# cybathlon_core.net
KiCad netlist of a schematic drawn in Altium Designer
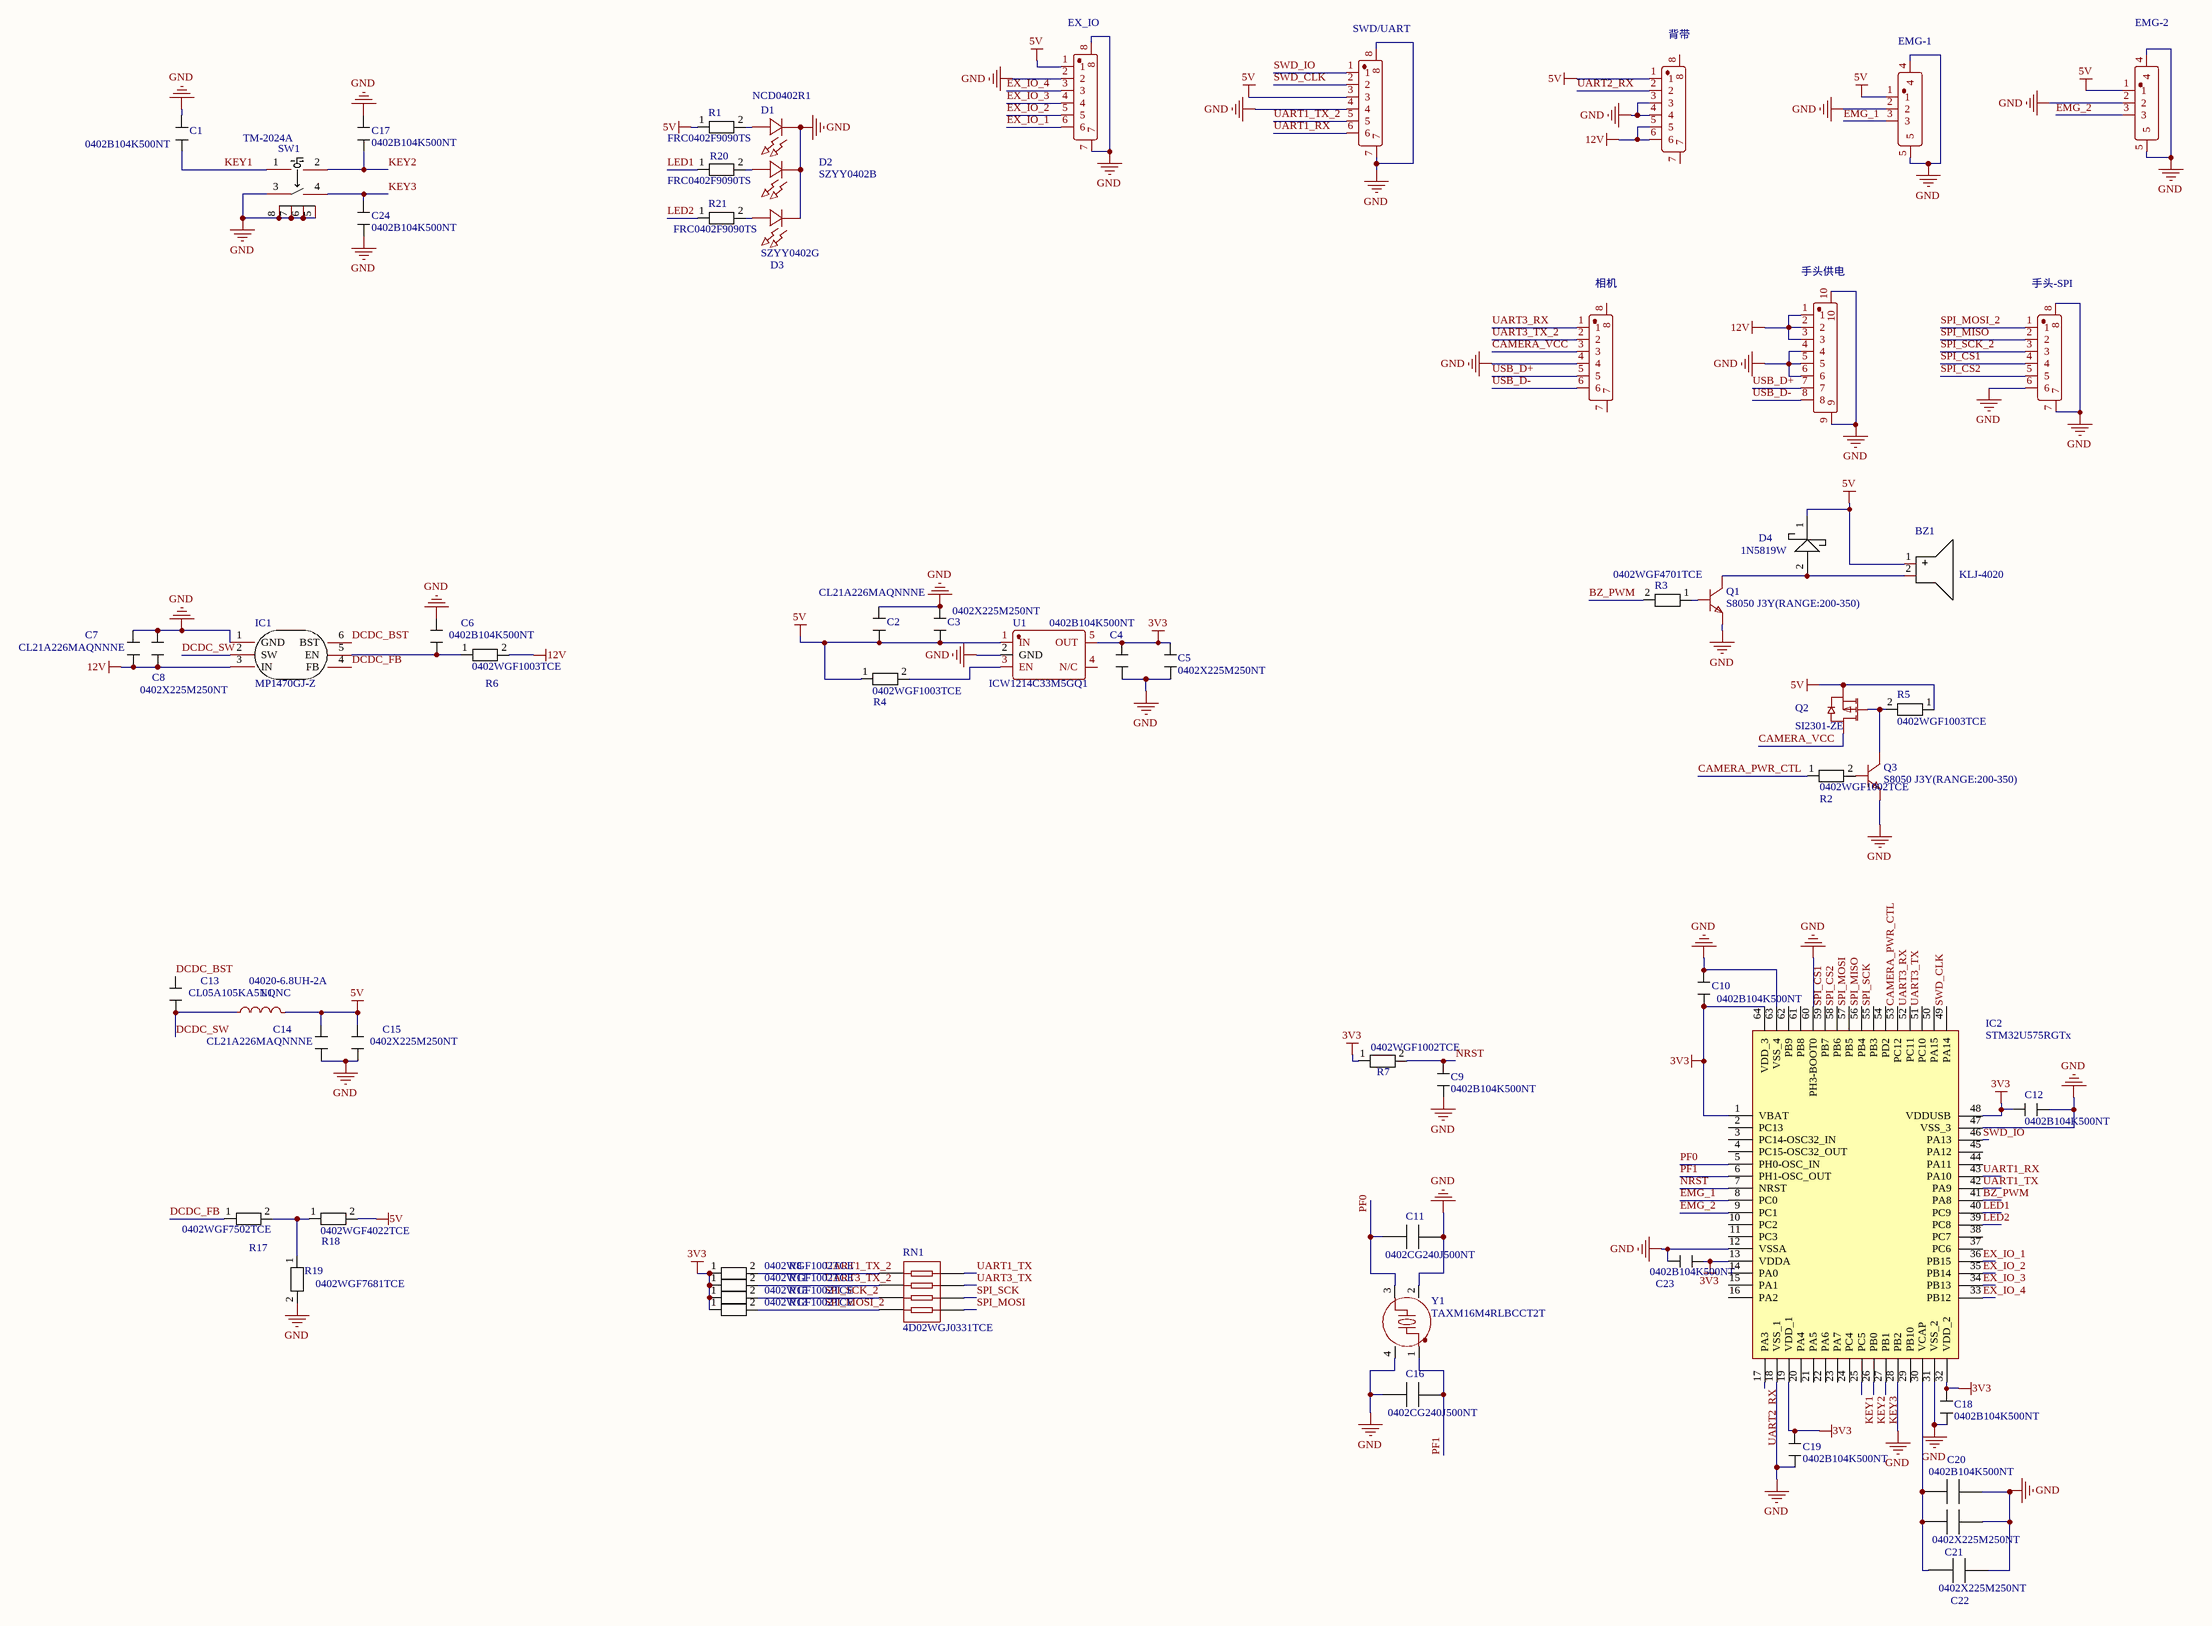
[diagram p0: cybathlon_core.SchDoc]

(export (version "E")
  (design (tool "Eeschema 10.0.6"))
  (components
    (comp (ref "BZ1")
      (value "KLJ-4020")
      (footprint "BUZ-SMD_L4.0-W4.0-P3.50-L")
      (libsource (lib "USER_RCL") (part "BUZZER_UNSOURCE"))
    )
    (comp (ref "C1") (value "0402B104K500NT") (footprint "CAP_0402") (libsource (lib "") (part "CAP_1")))
    (comp (ref "C2") (value "CL21A226MAQNNNE") (footprint "CAP_0805") (libsource (lib "") (part "CAP_1")))
    (comp (ref "C3") (value "0402X225M250NT") (footprint "CAP_0402") (libsource (lib "") (part "CAP_1")))
    (comp (ref "C4") (value "0402B104K500NT") (footprint "CAP_0402") (libsource (lib "") (part "CAP_1")))
    (comp (ref "C5") (value "0402X225M250NT") (footprint "CAP_0402") (libsource (lib "") (part "CAP_1")))
    (comp (ref "C6") (value "0402B104K500NT") (footprint "CAP_0402") (libsource (lib "") (part "CAP_1")))
    (comp (ref "C7") (value "CL21A226MAQNNNE") (footprint "CAP_0805") (libsource (lib "") (part "CAP_1")))
    (comp (ref "C8") (value "0402X225M250NT") (footprint "CAP_0402") (libsource (lib "") (part "CAP_1")))
    (comp (ref "C9") (value "0402B104K500NT") (footprint "CAP_0402") (libsource (lib "") (part "CAP_1")))
    (comp (ref "C10") (value "0402B104K500NT") (footprint "CAP_0402") (libsource (lib "") (part "CAP_1")))
    (comp (ref "C11")
      (value "0402CG240J500NT")
      (footprint "CAP_0402")
      (libsource (lib "USER_RCL") (part "CAP"))
    )
    (comp (ref "C12") (value "0402B104K500NT") (footprint "CAP_0402") (libsource (lib "") (part "CAP_1")))
    (comp (ref "C13") (value "CL05A105KA5NQNC") (footprint "CAP_0402") (libsource (lib "") (part "CAP_1")))
    (comp (ref "C14") (value "CL21A226MAQNNNE") (footprint "CAP_0805") (libsource (lib "") (part "CAP_1")))
    (comp (ref "C15") (value "0402X225M250NT") (footprint "CAP_0402") (libsource (lib "") (part "CAP_1")))
    (comp (ref "C16")
      (value "0402CG240J500NT")
      (footprint "CAP_0402")
      (libsource (lib "USER_RCL") (part "CAP"))
    )
    (comp (ref "C17") (value "0402B104K500NT") (footprint "CAP_0402") (libsource (lib "") (part "CAP_1")))
    (comp (ref "C18") (value "0402B104K500NT") (footprint "CAP_0402") (libsource (lib "") (part "CAP_1")))
    (comp (ref "C19") (value "0402B104K500NT") (footprint "CAP_0402") (libsource (lib "") (part "CAP_1")))
    (comp (ref "C20")
      (value "0402B104K500NT")
      (footprint "CAP_0402")
      (libsource (lib "USER_RCL") (part "CAP"))
    )
    (comp (ref "C21")
      (value "0402X225M250NT")
      (footprint "CAP_0402")
      (libsource (lib "USER_RCL") (part "CAP"))
    )
    (comp (ref "C22")
      (value "0402X225M250NT")
      (footprint "CAP_0402")
      (libsource (lib "USER_RCL") (part "CAP"))
    )
    (comp (ref "C23") (value "0402B104K500NT") (footprint "CAP_0402") (libsource (lib "") (part "CAP_1")))
    (comp (ref "C24") (value "0402B104K500NT") (footprint "CAP_0402") (libsource (lib "") (part "CAP_1")))
    (comp (ref "D1") (value "NCD0402R1") (footprint "LED0603-RD") (libsource (lib "USER_LED") (part "LED")))
    (comp (ref "D2") (value "SZYY0402B") (footprint "LED0603-RD") (libsource (lib "USER_LED") (part "LED")))
    (comp (ref "D3") (value "SZYY0402G") (footprint "LED0603-RD") (libsource (lib "USER_LED") (part "LED")))
    (comp (ref "D4")
      (value "1N5819W")
      (footprint "SHOTTKY DIODE_SOD-123")
      (libsource (lib "USER_RCL") (part "SHOTTKY DIODE"))
    )
    (comp (ref "IC1")
      (value "MP1470GJ-Z")
      (footprint "SOT-23-6_L2.9-W1.6-P0.95-LS2.8-BR")
      (libsource (lib "USER_IC") (part "MP1470GJ-Z"))
    )
    (comp (ref "IC2")
      (value "STM32U575RGTx")
      (footprint "STM32U575RGTx")
      (description "STM32U575RGT6")
      (libsource (lib "USER_IC") (part "STM32U575RGTx"))
    )
    (comp (ref "L1")
      (value "04020-6.8UH-2A")
      (footprint "L_04020_L4.1_W4.6")
      (libsource (lib "USER_RCL") (part "INDUCTANCE"))
    )
    (comp (ref "P1")
      (value "背带")
      (footprint "CONN-SMD_3P-P1.50_1.5-6P-WTDK")
      (libsource (lib "USER_PORT") (part "6P"))
    )
    (comp (ref "P2")
      (value "SWD/UART")
      (footprint "CONN-SMD_6P-P1.00_XUNPU_WAFER-SH1.0-6PWB")
      (libsource (lib "USER_PORT") (part "6P"))
    )
    (comp (ref "P4")
      (value "EMG-1")
      (footprint "CONN-SMD_3P-P1.0-HC-1.0-3PWT")
      (libsource (lib "USER_PORT") (part "3P"))
    )
    (comp (ref "P5")
      (value "EMG-2")
      (footprint "CONN-SMD_3P-P1.0-HC-1.0-3PWT")
      (libsource (lib "USER_PORT") (part "3P"))
    )
    (comp (ref "P6")
      (value "EX_IO")
      (footprint "CONN-SMD_6P-P1.00_XUNPU_WAFER-SH1.0-6PWB")
      (libsource (lib "USER_PORT") (part "6P"))
    )
    (comp (ref "P7")
      (value "手头供电")
      (footprint "CONN-SMD_8P-P1.00_XUNPU_WAFER-SH1.0-8PWB")
      (libsource (lib "USER_PORT") (part "8P"))
    )
    (comp (ref "P8")
      (value "相机")
      (footprint "CONN-SMD_3P-P1.50_1.5-6P-WTDK")
      (libsource (lib "USER_PORT") (part "6P"))
    )
    (comp (ref "P9")
      (value "手头-SPI")
      (footprint "CONN-SMD_6P-P1.00_XUNPU_WAFER-SH1.0-6PWB")
      (libsource (lib "USER_PORT") (part "6P"))
    )
    (comp (ref "Q1")
      (value "S8050 J3Y(RANGE:200-350)")
      (footprint "SOT-23")
      (libsource (lib "USER_TRANSISTOR") (part "NPN"))
    )
    (comp (ref "Q2") (value "SI2301-ZE") (footprint "SOT-23") (libsource (lib "USER_SWITCH") (part "PMOS")))
    (comp (ref "Q3")
      (value "S8050 J3Y(RANGE:200-350)")
      (footprint "SOT-23")
      (libsource (lib "USER_TRANSISTOR") (part "NPN"))
    )
    (comp (ref "R1")
      (value "FRC0402F9090TS")
      (footprint "RES_0402")
      (libsource (lib "USER_RCL") (part "RES"))
    )
    (comp (ref "R2")
      (value "0402WGF1002TCE")
      (footprint "RES_0402")
      (libsource (lib "USER_RCL") (part "RES"))
    )
    (comp (ref "R3")
      (value "0402WGF4701TCE")
      (footprint "RES_0402")
      (libsource (lib "USER_RCL") (part "RES"))
    )
    (comp (ref "R4")
      (value "0402WGF1003TCE")
      (footprint "RES_0402")
      (libsource (lib "USER_RCL") (part "RES"))
    )
    (comp (ref "R5")
      (value "0402WGF1003TCE")
      (footprint "RES_0402")
      (libsource (lib "USER_RCL") (part "RES"))
    )
    (comp (ref "R6")
      (value "0402WGF1003TCE")
      (footprint "RES_0402")
      (libsource (lib "USER_RCL") (part "RES"))
    )
    (comp (ref "R7")
      (value "0402WGF1002TCE")
      (footprint "RES_0402")
      (libsource (lib "USER_RCL") (part "RES"))
    )
    (comp (ref "R8")
      (value "0402WGF1002TCE")
      (footprint "RES_0402")
      (libsource (lib "USER_RCL") (part "RES"))
    )
    (comp (ref "R11")
      (value "0402WGF1002TCE")
      (footprint "RES_0402")
      (libsource (lib "USER_RCL") (part "RES"))
    )
    (comp (ref "R13")
      (value "0402WGF1002TCE")
      (footprint "RES_0402")
      (libsource (lib "USER_RCL") (part "RES"))
    )
    (comp (ref "R15")
      (value "0402WGF1002TCE")
      (footprint "RES_0402")
      (libsource (lib "USER_RCL") (part "RES"))
    )
    (comp (ref "R17")
      (value "0402WGF7502TCE")
      (footprint "RES_0402")
      (libsource (lib "USER_RCL") (part "RES"))
    )
    (comp (ref "R18")
      (value "0402WGF4022TCE")
      (footprint "RES_0402")
      (libsource (lib "USER_RCL") (part "RES"))
    )
    (comp (ref "R19")
      (value "0402WGF7681TCE")
      (footprint "RES_0402")
      (libsource (lib "USER_RCL") (part "RES"))
    )
    (comp (ref "R20")
      (value "FRC0402F9090TS")
      (footprint "RES_0402")
      (libsource (lib "USER_RCL") (part "RES"))
    )
    (comp (ref "R21")
      (value "FRC0402F9090TS")
      (footprint "RES_0402")
      (libsource (lib "USER_RCL") (part "RES"))
    )
    (comp (ref "RN1")
      (value "4D02WGJ0331TCE")
      (footprint "RES_0402_4P")
      (libsource (lib "USER_RCL") (part "RES_4P"))
    )
    (comp (ref "SW1")
      (value "TM-2024A")
      (footprint "SW-SMD_TM-2024A")
      (libsource (lib "USER_SWITCH") (part "WHEEL_SWITCH"))
    )
    (comp (ref "U1")
      (value "ICW1214C33M5GQ1")
      (footprint "SOT-23-5_L3.0-W1.7-P0.95-LS2.8-BL")
      (libsource (lib "USER_IC") (part "SGM2210"))
    )
    (comp (ref "Y1")
      (value "TAXM16M4RLBCCT2T")
      (footprint "OSC_3225")
      (libsource (lib "USER_TRANSISTOR") (part "OSC"))
    )
  )
  (nets
    (net (code "1") (name "/BZ_PWM") (class "Default")
      (node (ref "IC2") (pin "41") (pinfunction "PA8_41") (pintype "passive"))
      (node (ref "R3") (pin "2") (pinfunction "2_2") (pintype "passive"))
    )
    (net (code "2") (name "/CAMERA_PWR_CTL") (class "Default")
      (node (ref "IC2") (pin "53") (pinfunction "PC12_53") (pintype "passive"))
      (node (ref "R2") (pin "1") (pinfunction "1_1") (pintype "passive"))
    )
    (net (code "3") (name "/CAMERA_VCC") (class "Default")
      (node (ref "P8") (pin "3") (pinfunction "3_3") (pintype "passive"))
      (node (ref "Q2") (pin "3") (pinfunction "D_3") (pintype "passive"))
    )
    (net (code "4") (name "/DCDC_BST") (class "Default")
      (node (ref "C13") (pin "1") (pinfunction "1_1") (pintype "passive"))
      (node (ref "IC1") (pin "6") (pinfunction "BST_6") (pintype "passive"))
    )
    (net (code "5") (name "/DCDC_FB") (class "Default")
      (node (ref "IC1") (pin "4") (pinfunction "FB_4") (pintype "passive"))
      (node (ref "R17") (pin "1") (pinfunction "1_1") (pintype "passive"))
    )
    (net (code "6") (name "/DCDC_SW") (class "Default")
      (node (ref "C13") (pin "2") (pinfunction "2_2") (pintype "passive"))
      (node (ref "IC1") (pin "2") (pinfunction "SW_2") (pintype "passive"))
      (node (ref "L1") (pin "1") (pinfunction "1_1") (pintype "passive"))
    )
    (net (code "7") (name "/EMG_1") (class "Default")
      (node (ref "IC2") (pin "8") (pinfunction "PC0_8") (pintype "passive"))
      (node (ref "P4") (pin "3") (pinfunction "3_3") (pintype "passive"))
    )
    (net (code "8") (name "/EMG_2") (class "Default")
      (node (ref "IC2") (pin "9") (pinfunction "PC1_9") (pintype "passive"))
      (node (ref "P5") (pin "3") (pinfunction "3_3") (pintype "passive"))
    )
    (net (code "9") (name "/EX_IO_1") (class "Default")
      (node (ref "IC2") (pin "36") (pinfunction "PB15_36") (pintype "passive"))
      (node (ref "P6") (pin "6") (pinfunction "6_6") (pintype "passive"))
    )
    (net (code "10") (name "/EX_IO_2") (class "Default")
      (node (ref "IC2") (pin "35") (pinfunction "PB14_35") (pintype "passive"))
      (node (ref "P6") (pin "5") (pinfunction "5_5") (pintype "passive"))
    )
    (net (code "11") (name "/EX_IO_3") (class "Default")
      (node (ref "IC2") (pin "34") (pinfunction "PB13_34") (pintype "passive"))
      (node (ref "P6") (pin "4") (pinfunction "4_4") (pintype "passive"))
    )
    (net (code "12") (name "/EX_IO_4") (class "Default")
      (node (ref "IC2") (pin "33") (pinfunction "PB12_33") (pintype "passive"))
      (node (ref "P6") (pin "3") (pinfunction "3_3") (pintype "passive"))
    )
    (net (code "13") (name "/KEY1") (class "Default")
      (node (ref "C1") (pin "1") (pinfunction "1_1") (pintype "passive"))
      (node (ref "IC2") (pin "25") (pinfunction "PC5_25") (pintype "passive"))
      (node (ref "SW1") (pin "1") (pinfunction "1_1") (pintype "passive"))
    )
    (net (code "14") (name "/KEY2") (class "Default")
      (node (ref "C17") (pin "1") (pinfunction "1_1") (pintype "passive"))
      (node (ref "IC2") (pin "26") (pinfunction "PB0_26") (pintype "passive"))
      (node (ref "SW1") (pin "2") (pinfunction "2_2") (pintype "passive"))
    )
    (net (code "15") (name "/KEY3") (class "Default")
      (node (ref "C24") (pin "2") (pinfunction "2_2") (pintype "passive"))
      (node (ref "IC2") (pin "27") (pinfunction "PB1_27") (pintype "passive"))
      (node (ref "SW1") (pin "4") (pinfunction "4_4") (pintype "passive"))
    )
    (net (code "16") (name "/LED1") (class "Default")
      (node (ref "IC2") (pin "40") (pinfunction "PC9_40") (pintype "passive"))
      (node (ref "R20") (pin "1") (pinfunction "1_1") (pintype "passive"))
    )
    (net (code "17") (name "/LED2") (class "Default")
      (node (ref "IC2") (pin "39") (pinfunction "PC8_39") (pintype "passive"))
      (node (ref "R21") (pin "1") (pinfunction "1_1") (pintype "passive"))
    )
    (net (code "18") (name "/NRST") (class "Default")
      (node (ref "C9") (pin "2") (pinfunction "2_2") (pintype "passive"))
      (node (ref "IC2") (pin "7") (pinfunction "NRST_7") (pintype "passive"))
      (node (ref "R7") (pin "2") (pinfunction "2_2") (pintype "passive"))
    )
    (net (code "19") (name "/PF0") (class "Default")
      (node (ref "C11") (pin "2") (pinfunction "2_2") (pintype "passive"))
      (node (ref "IC2") (pin "5") (pinfunction "PH0-OSC_IN_5") (pintype "passive"))
      (node (ref "Y1") (pin "3") (pinfunction "3_3") (pintype "passive"))
    )
    (net (code "20") (name "/PF1") (class "Default")
      (node (ref "C16") (pin "1") (pinfunction "1_1") (pintype "passive"))
      (node (ref "IC2") (pin "6") (pinfunction "PH1-OSC_OUT_6") (pintype "passive"))
      (node (ref "Y1") (pin "1") (pinfunction "1_1") (pintype "passive"))
    )
    (net (code "21") (name "/SPI_CS1") (class "Default")
      (node (ref "IC2") (pin "59") (pinfunction "PB7_59") (pintype "passive"))
      (node (ref "P9") (pin "4") (pinfunction "4_4") (pintype "passive"))
    )
    (net (code "22") (name "/SPI_CS2") (class "Default")
      (node (ref "IC2") (pin "58") (pinfunction "PB6_58") (pintype "passive"))
      (node (ref "P9") (pin "5") (pinfunction "5_5") (pintype "passive"))
    )
    (net (code "23") (name "/SPI_MISO") (class "Default")
      (node (ref "IC2") (pin "56") (pinfunction "PB4_56") (pintype "passive"))
      (node (ref "P9") (pin "2") (pinfunction "2_2") (pintype "passive"))
    )
    (net (code "24") (name "/SPI_MOSI") (class "Default")
      (node (ref "IC2") (pin "57") (pinfunction "PB5_57") (pintype "passive"))
      (node (ref "RN1") (pin "5") (pinfunction "5_5") (pintype "passive"))
    )
    (net (code "25") (name "/SPI_MOSI_2") (class "Default")
      (node (ref "P9") (pin "1") (pinfunction "1_1") (pintype "passive"))
      (node (ref "R13") (pin "2") (pinfunction "2_2") (pintype "passive"))
      (node (ref "RN1") (pin "4") (pinfunction "4_4") (pintype "passive"))
    )
    (net (code "26") (name "/SPI_SCK") (class "Default")
      (node (ref "IC2") (pin "55") (pinfunction "PB3_55") (pintype "passive"))
      (node (ref "RN1") (pin "6") (pinfunction "6_6") (pintype "passive"))
    )
    (net (code "27") (name "/SPI_SCK_2") (class "Default")
      (node (ref "P9") (pin "3") (pinfunction "3_3") (pintype "passive"))
      (node (ref "R15") (pin "2") (pinfunction "2_2") (pintype "passive"))
      (node (ref "RN1") (pin "3") (pinfunction "3_3") (pintype "passive"))
    )
    (net (code "28") (name "/SWD_CLK") (class "Default")
      (node (ref "IC2") (pin "49") (pinfunction "PA14_49") (pintype "passive"))
      (node (ref "P2") (pin "2") (pinfunction "2_2") (pintype "passive"))
    )
    (net (code "29") (name "/SWD_IO") (class "Default")
      (node (ref "IC2") (pin "46") (pinfunction "PA13_46") (pintype "passive"))
      (node (ref "P2") (pin "1") (pinfunction "1_1") (pintype "passive"))
    )
    (net (code "30") (name "/UART1_RX") (class "Default")
      (node (ref "IC2") (pin "43") (pinfunction "PA10_43") (pintype "passive"))
      (node (ref "P2") (pin "6") (pinfunction "6_6") (pintype "passive"))
    )
    (net (code "31") (name "/UART1_TX") (class "Default")
      (node (ref "IC2") (pin "42") (pinfunction "PA9_42") (pintype "passive"))
      (node (ref "RN1") (pin "8") (pinfunction "8_8") (pintype "passive"))
    )
    (net (code "32") (name "/UART1_TX_2") (class "Default")
      (node (ref "P2") (pin "5") (pinfunction "5_5") (pintype "passive"))
      (node (ref "R8") (pin "2") (pinfunction "2_2") (pintype "passive"))
      (node (ref "RN1") (pin "1") (pinfunction "1_1") (pintype "passive"))
    )
    (net (code "33") (name "/UART2_RX") (class "Default")
      (node (ref "IC2") (pin "17") (pinfunction "PA3_17") (pintype "passive"))
      (node (ref "P1") (pin "2") (pinfunction "2_2") (pintype "passive"))
    )
    (net (code "34") (name "/UART3_RX") (class "Default")
      (node (ref "IC2") (pin "52") (pinfunction "PC11_52") (pintype "passive"))
      (node (ref "P8") (pin "1") (pinfunction "1_1") (pintype "passive"))
    )
    (net (code "35") (name "/UART3_TX") (class "Default")
      (node (ref "IC2") (pin "51") (pinfunction "PC10_51") (pintype "passive"))
      (node (ref "RN1") (pin "7") (pinfunction "7_7") (pintype "passive"))
    )
    (net (code "36") (name "/UART3_TX_2") (class "Default")
      (node (ref "P8") (pin "2") (pinfunction "2_2") (pintype "passive"))
      (node (ref "R11") (pin "2") (pinfunction "2_2") (pintype "passive"))
      (node (ref "RN1") (pin "2") (pinfunction "2_2") (pintype "passive"))
    )
    (net (code "37") (name "/USB_D+") (class "Default")
      (node (ref "P7") (pin "7") (pinfunction "7_7") (pintype "passive"))
      (node (ref "P8") (pin "5") (pinfunction "5_5") (pintype "passive"))
    )
    (net (code "38") (name "/USB_D-") (class "Default")
      (node (ref "P7") (pin "8") (pinfunction "8_8") (pintype "passive"))
      (node (ref "P8") (pin "6") (pinfunction "6_6") (pintype "passive"))
    )
    (net (code "39") (name "3V3") (class "Default")
      (node (ref "C10") (pin "2") (pinfunction "2_2") (pintype "passive"))
      (node (ref "C12") (pin "2") (pinfunction "2_2") (pintype "passive"))
      (node (ref "C18") (pin "2") (pinfunction "2_2") (pintype "passive"))
      (node (ref "C19") (pin "2") (pinfunction "2_2") (pintype "passive"))
      (node (ref "C23") (pin "2") (pinfunction "2_2") (pintype "passive"))
      (node (ref "C4") (pin "1") (pinfunction "1_1") (pintype "passive"))
      (node (ref "C5") (pin "1") (pinfunction "1_1") (pintype "passive"))
      (node (ref "IC2") (pin "1") (pinfunction "VBAT_1") (pintype "passive"))
      (node (ref "IC2") (pin "13") (pinfunction "VDDA_13") (pintype "passive"))
      (node (ref "IC2") (pin "19") (pinfunction "VDD_1_19") (pintype "passive"))
      (node (ref "IC2") (pin "32") (pinfunction "VDD_2_32") (pintype "passive"))
      (node (ref "IC2") (pin "48") (pinfunction "VDDUSB_48") (pintype "passive"))
      (node (ref "IC2") (pin "64") (pinfunction "VDD_3_64") (pintype "passive"))
      (node (ref "R11") (pin "1") (pinfunction "1_1") (pintype "passive"))
      (node (ref "R13") (pin "1") (pinfunction "1_1") (pintype "passive"))
      (node (ref "R15") (pin "1") (pinfunction "1_1") (pintype "passive"))
      (node (ref "R7") (pin "1") (pinfunction "1_1") (pintype "passive"))
      (node (ref "R8") (pin "1") (pinfunction "1_1") (pintype "passive"))
      (node (ref "U1") (pin "5") (pinfunction "OUT_5") (pintype "passive"))
    )
    (net (code "40") (name "5V") (class "Default")
      (node (ref "BZ1") (pin "1") (pinfunction "+_1") (pintype "passive"))
      (node (ref "C14") (pin "1") (pinfunction "1_1") (pintype "passive"))
      (node (ref "C15") (pin "1") (pinfunction "1_1") (pintype "passive"))
      (node (ref "C2") (pin "2") (pinfunction "2_2") (pintype "passive"))
      (node (ref "C3") (pin "2") (pinfunction "2_2") (pintype "passive"))
      (node (ref "D4") (pin "1") (pinfunction "1_1") (pintype "passive"))
      (node (ref "L1") (pin "2") (pinfunction "2_2") (pintype "passive"))
      (node (ref "P1") (pin "1") (pinfunction "1_1") (pintype "passive"))
      (node (ref "P2") (pin "3") (pinfunction "3_3") (pintype "passive"))
      (node (ref "P4") (pin "1") (pinfunction "1_1") (pintype "passive"))
      (node (ref "P5") (pin "1") (pinfunction "1_1") (pintype "passive"))
      (node (ref "P6") (pin "1") (pinfunction "1_1") (pintype "passive"))
      (node (ref "Q2") (pin "2") (pinfunction "S_2") (pintype "passive"))
      (node (ref "R1") (pin "1") (pinfunction "1_1") (pintype "passive"))
      (node (ref "R18") (pin "2") (pinfunction "2_2") (pintype "passive"))
      (node (ref "R4") (pin "1") (pinfunction "1_1") (pintype "passive"))
      (node (ref "R5") (pin "1") (pinfunction "1_1") (pintype "passive"))
      (node (ref "U1") (pin "1") (pinfunction "IN_1") (pintype "passive"))
    )
    (net (code "41") (name "12V") (class "Default")
      (node (ref "C7") (pin "2") (pinfunction "2_2") (pintype "passive"))
      (node (ref "C8") (pin "2") (pinfunction "2_2") (pintype "passive"))
      (node (ref "IC1") (pin "3") (pinfunction "IN_3") (pintype "passive"))
      (node (ref "P1") (pin "5") (pinfunction "5_5") (pintype "passive"))
      (node (ref "P1") (pin "6") (pinfunction "6_6") (pintype "passive"))
      (node (ref "P7") (pin "1") (pinfunction "1_1") (pintype "passive"))
      (node (ref "P7") (pin "2") (pinfunction "2_2") (pintype "passive"))
      (node (ref "P7") (pin "3") (pinfunction "3_3") (pintype "passive"))
      (node (ref "R6") (pin "2") (pinfunction "2_2") (pintype "passive"))
    )
    (net (code "42") (name "GND") (class "Default")
      (node (ref "C1") (pin "2") (pinfunction "2_2") (pintype "passive"))
      (node (ref "C10") (pin "1") (pinfunction "1_1") (pintype "passive"))
      (node (ref "C11") (pin "1") (pinfunction "1_1") (pintype "passive"))
      (node (ref "C12") (pin "1") (pinfunction "1_1") (pintype "passive"))
      (node (ref "C14") (pin "2") (pinfunction "2_2") (pintype "passive"))
      (node (ref "C15") (pin "2") (pinfunction "2_2") (pintype "passive"))
      (node (ref "C16") (pin "2") (pinfunction "2_2") (pintype "passive"))
      (node (ref "C17") (pin "2") (pinfunction "2_2") (pintype "passive"))
      (node (ref "C18") (pin "1") (pinfunction "1_1") (pintype "passive"))
      (node (ref "C19") (pin "1") (pinfunction "1_1") (pintype "passive"))
      (node (ref "C2") (pin "1") (pinfunction "1_1") (pintype "passive"))
      (node (ref "C20") (pin "2") (pinfunction "2_2") (pintype "passive"))
      (node (ref "C21") (pin "2") (pinfunction "2_2") (pintype "passive"))
      (node (ref "C22") (pin "2") (pinfunction "2_2") (pintype "passive"))
      (node (ref "C23") (pin "1") (pinfunction "1_1") (pintype "passive"))
      (node (ref "C24") (pin "1") (pinfunction "1_1") (pintype "passive"))
      (node (ref "C3") (pin "1") (pinfunction "1_1") (pintype "passive"))
      (node (ref "C4") (pin "2") (pinfunction "2_2") (pintype "passive"))
      (node (ref "C5") (pin "2") (pinfunction "2_2") (pintype "passive"))
      (node (ref "C6") (pin "1") (pinfunction "1_1") (pintype "passive"))
      (node (ref "C7") (pin "1") (pinfunction "1_1") (pintype "passive"))
      (node (ref "C8") (pin "1") (pinfunction "1_1") (pintype "passive"))
      (node (ref "C9") (pin "1") (pinfunction "1_1") (pintype "passive"))
      (node (ref "D1") (pin "2") (pinfunction "-_2") (pintype "passive"))
      (node (ref "D2") (pin "2") (pinfunction "-_2") (pintype "passive"))
      (node (ref "D3") (pin "2") (pinfunction "-_2") (pintype "passive"))
      (node (ref "IC1") (pin "1") (pinfunction "GND_1") (pintype "passive"))
      (node (ref "IC2") (pin "12") (pinfunction "VSSA_12") (pintype "passive"))
      (node (ref "IC2") (pin "18") (pinfunction "VSS_1_18") (pintype "passive"))
      (node (ref "IC2") (pin "28") (pinfunction "PB2_28") (pintype "passive"))
      (node (ref "IC2") (pin "31") (pinfunction "VSS_2_31") (pintype "passive"))
      (node (ref "IC2") (pin "47") (pinfunction "VSS_3_47") (pintype "passive"))
      (node (ref "IC2") (pin "60") (pinfunction "PH3-BOOT0_60") (pintype "passive"))
      (node (ref "IC2") (pin "63") (pinfunction "VSS_4_63") (pintype "passive"))
      (node (ref "P1") (pin "3") (pinfunction "3_3") (pintype "passive"))
      (node (ref "P1") (pin "4") (pinfunction "4_4") (pintype "passive"))
      (node (ref "P2") (pin "4") (pinfunction "4_4") (pintype "passive"))
      (node (ref "P2") (pin "7") (pinfunction "7_7") (pintype "passive"))
      (node (ref "P2") (pin "8") (pinfunction "8_8") (pintype "passive"))
      (node (ref "P4") (pin "2") (pinfunction "2_2") (pintype "passive"))
      (node (ref "P4") (pin "4") (pinfunction "4_4") (pintype "passive"))
      (node (ref "P4") (pin "5") (pinfunction "5_5") (pintype "passive"))
      (node (ref "P5") (pin "2") (pinfunction "2_2") (pintype "passive"))
      (node (ref "P5") (pin "4") (pinfunction "4_4") (pintype "passive"))
      (node (ref "P5") (pin "5") (pinfunction "5_5") (pintype "passive"))
      (node (ref "P6") (pin "2") (pinfunction "2_2") (pintype "passive"))
      (node (ref "P6") (pin "7") (pinfunction "7_7") (pintype "passive"))
      (node (ref "P6") (pin "8") (pinfunction "8_8") (pintype "passive"))
      (node (ref "P7") (pin "10") (pinfunction "10_10") (pintype "passive"))
      (node (ref "P7") (pin "4") (pinfunction "4_4") (pintype "passive"))
      (node (ref "P7") (pin "5") (pinfunction "5_5") (pintype "passive"))
      (node (ref "P7") (pin "6") (pinfunction "6_6") (pintype "passive"))
      (node (ref "P7") (pin "9") (pinfunction "9_9") (pintype "passive"))
      (node (ref "P8") (pin "4") (pinfunction "4_4") (pintype "passive"))
      (node (ref "P9") (pin "6") (pinfunction "6_6") (pintype "passive"))
      (node (ref "P9") (pin "7") (pinfunction "7_7") (pintype "passive"))
      (node (ref "P9") (pin "8") (pinfunction "8_8") (pintype "passive"))
      (node (ref "Q1") (pin "2") (pinfunction "E_2") (pintype "passive"))
      (node (ref "Q3") (pin "2") (pinfunction "E_2") (pintype "passive"))
      (node (ref "R19") (pin "2") (pinfunction "2_2") (pintype "passive"))
      (node (ref "SW1") (pin "3") (pinfunction "3_3") (pintype "passive"))
      (node (ref "SW1") (pin "5") (pinfunction "5_5") (pintype "passive"))
      (node (ref "SW1") (pin "6") (pinfunction "6_6") (pintype "passive"))
      (node (ref "SW1") (pin "7") (pinfunction "7_7") (pintype "passive"))
      (node (ref "SW1") (pin "8") (pinfunction "8_8") (pintype "passive"))
      (node (ref "U1") (pin "2") (pinfunction "GND_2") (pintype "passive"))
      (node (ref "Y1") (pin "2") (pinfunction "GND_2") (pintype "passive"))
      (node (ref "Y1") (pin "4") (pinfunction "GND_4") (pintype "passive"))
    )
    (net (code "43") (name "Net-(BZ1--)") (class "Default")
      (node (ref "BZ1") (pin "2") (pinfunction "-_2") (pintype "passive"))
      (node (ref "D4") (pin "2") (pinfunction "2_2") (pintype "passive"))
      (node (ref "Q1") (pin "3") (pinfunction "C_3") (pintype "passive"))
    )
    (net (code "44") (name "Net-(D1-+)") (class "Default")
      (node (ref "D1") (pin "1") (pinfunction "+_1") (pintype "passive"))
      (node (ref "R1") (pin "2") (pinfunction "2_2") (pintype "passive"))
    )
    (net (code "45") (name "Net-(D2-+)") (class "Default")
      (node (ref "D2") (pin "1") (pinfunction "+_1") (pintype "passive"))
      (node (ref "R20") (pin "2") (pinfunction "2_2") (pintype "passive"))
    )
    (net (code "46") (name "Net-(D3-+)") (class "Default")
      (node (ref "D3") (pin "1") (pinfunction "+_1") (pintype "passive"))
      (node (ref "R21") (pin "2") (pinfunction "2_2") (pintype "passive"))
    )
    (net (code "47") (name "Net-(IC1-EN)") (class "Default")
      (node (ref "C6") (pin "2") (pinfunction "2_2") (pintype "passive"))
      (node (ref "IC1") (pin "5") (pinfunction "EN_5") (pintype "passive"))
      (node (ref "R6") (pin "1") (pinfunction "1_1") (pintype "passive"))
    )
    (net (code "48") (name "Net-(IC2-VCAP)") (class "Default")
      (node (ref "C20") (pin "1") (pinfunction "1_1") (pintype "passive"))
      (node (ref "C21") (pin "1") (pinfunction "1_1") (pintype "passive"))
      (node (ref "C22") (pin "1") (pinfunction "1_1") (pintype "passive"))
      (node (ref "IC2") (pin "30") (pinfunction "VCAP_30") (pintype "passive"))
    )
    (net (code "49") (name "Net-(Q1-B)") (class "Default")
      (node (ref "Q1") (pin "1") (pinfunction "B_1") (pintype "passive"))
      (node (ref "R3") (pin "1") (pinfunction "1_1") (pintype "passive"))
    )
    (net (code "50") (name "Net-(Q2-G)") (class "Default")
      (node (ref "Q2") (pin "1") (pinfunction "G_1") (pintype "passive"))
      (node (ref "Q3") (pin "3") (pinfunction "C_3") (pintype "passive"))
      (node (ref "R5") (pin "2") (pinfunction "2_2") (pintype "passive"))
    )
    (net (code "51") (name "Net-(Q3-B)") (class "Default")
      (node (ref "Q3") (pin "1") (pinfunction "B_1") (pintype "passive"))
      (node (ref "R2") (pin "2") (pinfunction "2_2") (pintype "passive"))
    )
    (net (code "52") (name "Net-(R17-Pad2)") (class "Default")
      (node (ref "R17") (pin "2") (pinfunction "2_2") (pintype "passive"))
      (node (ref "R18") (pin "1") (pinfunction "1_1") (pintype "passive"))
      (node (ref "R19") (pin "1") (pinfunction "1_1") (pintype "passive"))
    )
    (net (code "53") (name "Net-(U1-EN)") (class "Default")
      (node (ref "R4") (pin "2") (pinfunction "2_2") (pintype "passive"))
      (node (ref "U1") (pin "3") (pinfunction "EN_3") (pintype "passive"))
    )
    (net (code "54") (name "unconnected-(IC2-PA0-Pad14)") (class "Default")
      (node (ref "IC2") (pin "14") (pinfunction "PA0_14") (pintype "passive"))
    )
    (net (code "55") (name "unconnected-(IC2-PA1-Pad15)") (class "Default")
      (node (ref "IC2") (pin "15") (pinfunction "PA1_15") (pintype "passive"))
    )
    (net (code "56") (name "unconnected-(IC2-PA2-Pad16)") (class "Default")
      (node (ref "IC2") (pin "16") (pinfunction "PA2_16") (pintype "passive"))
    )
    (net (code "57") (name "unconnected-(IC2-PA4-Pad20)") (class "Default")
      (node (ref "IC2") (pin "20") (pinfunction "PA4_20") (pintype "passive"))
    )
    (net (code "58") (name "unconnected-(IC2-PA5-Pad21)") (class "Default")
      (node (ref "IC2") (pin "21") (pinfunction "PA5_21") (pintype "passive"))
    )
    (net (code "59") (name "unconnected-(IC2-PA6-Pad22)") (class "Default")
      (node (ref "IC2") (pin "22") (pinfunction "PA6_22") (pintype "passive"))
    )
    (net (code "60") (name "unconnected-(IC2-PA7-Pad23)") (class "Default")
      (node (ref "IC2") (pin "23") (pinfunction "PA7_23") (pintype "passive"))
    )
    (net (code "61") (name "unconnected-(IC2-PA11-Pad44)") (class "Default")
      (node (ref "IC2") (pin "44") (pinfunction "PA11_44") (pintype "passive"))
    )
    (net (code "62") (name "unconnected-(IC2-PA12-Pad45)") (class "Default")
      (node (ref "IC2") (pin "45") (pinfunction "PA12_45") (pintype "passive"))
    )
    (net (code "63") (name "unconnected-(IC2-PA15-Pad50)") (class "Default")
      (node (ref "IC2") (pin "50") (pinfunction "PA15_50") (pintype "passive"))
    )
    (net (code "64") (name "unconnected-(IC2-PB8-Pad61)") (class "Default")
      (node (ref "IC2") (pin "61") (pinfunction "PB8_61") (pintype "passive"))
    )
    (net (code "65") (name "unconnected-(IC2-PB9-Pad62)") (class "Default")
      (node (ref "IC2") (pin "62") (pinfunction "PB9_62") (pintype "passive"))
    )
    (net (code "66") (name "unconnected-(IC2-PB10-Pad29)") (class "Default")
      (node (ref "IC2") (pin "29") (pinfunction "PB10_29") (pintype "passive"))
    )
    (net (code "67") (name "unconnected-(IC2-PC2-Pad10)") (class "Default")
      (node (ref "IC2") (pin "10") (pinfunction "PC2_10") (pintype "passive"))
    )
    (net (code "68") (name "unconnected-(IC2-PC3-Pad11)") (class "Default")
      (node (ref "IC2") (pin "11") (pinfunction "PC3_11") (pintype "passive"))
    )
    (net (code "69") (name "unconnected-(IC2-PC4-Pad24)") (class "Default")
      (node (ref "IC2") (pin "24") (pinfunction "PC4_24") (pintype "passive"))
    )
    (net (code "70") (name "unconnected-(IC2-PC6-Pad37)") (class "Default")
      (node (ref "IC2") (pin "37") (pinfunction "PC6_37") (pintype "passive"))
    )
    (net (code "71") (name "unconnected-(IC2-PC7-Pad38)") (class "Default")
      (node (ref "IC2") (pin "38") (pinfunction "PC7_38") (pintype "passive"))
    )
    (net (code "72") (name "unconnected-(IC2-PC13-Pad2)") (class "Default")
      (node (ref "IC2") (pin "2") (pinfunction "PC13_2") (pintype "passive"))
    )
    (net (code "73") (name "unconnected-(IC2-PC14-OSC32_IN-Pad3)") (class "Default")
      (node (ref "IC2") (pin "3") (pinfunction "PC14-OSC32_IN_3") (pintype "passive"))
    )
    (net (code "74") (name "unconnected-(IC2-PC15-OSC32_OUT-Pad4)") (class "Default")
      (node (ref "IC2") (pin "4") (pinfunction "PC15-OSC32_OUT_4") (pintype "passive"))
    )
    (net (code "75") (name "unconnected-(IC2-PD2-Pad54)") (class "Default")
      (node (ref "IC2") (pin "54") (pinfunction "PD2_54") (pintype "passive"))
    )
    (net (code "76") (name "unconnected-(P1-Pad7)") (class "Default")
      (node (ref "P1") (pin "7") (pinfunction "7_7") (pintype "passive"))
    )
    (net (code "77") (name "unconnected-(P1-Pad8)") (class "Default")
      (node (ref "P1") (pin "8") (pinfunction "8_8") (pintype "passive"))
    )
    (net (code "78") (name "unconnected-(P8-Pad7)") (class "Default")
      (node (ref "P8") (pin "7") (pinfunction "7_7") (pintype "passive"))
    )
    (net (code "79") (name "unconnected-(P8-Pad8)") (class "Default")
      (node (ref "P8") (pin "8") (pinfunction "8_8") (pintype "passive"))
    )
    (net (code "80") (name "unconnected-(U1-N{slash}C-Pad4)") (class "Default")
      (node (ref "U1") (pin "4") (pinfunction "N/C_4") (pintype "passive"))
    )
  )
)
